# Qwiic_Joystick_v1_1_1.net
KiCad netlist of a schematic drawn in EAGLE
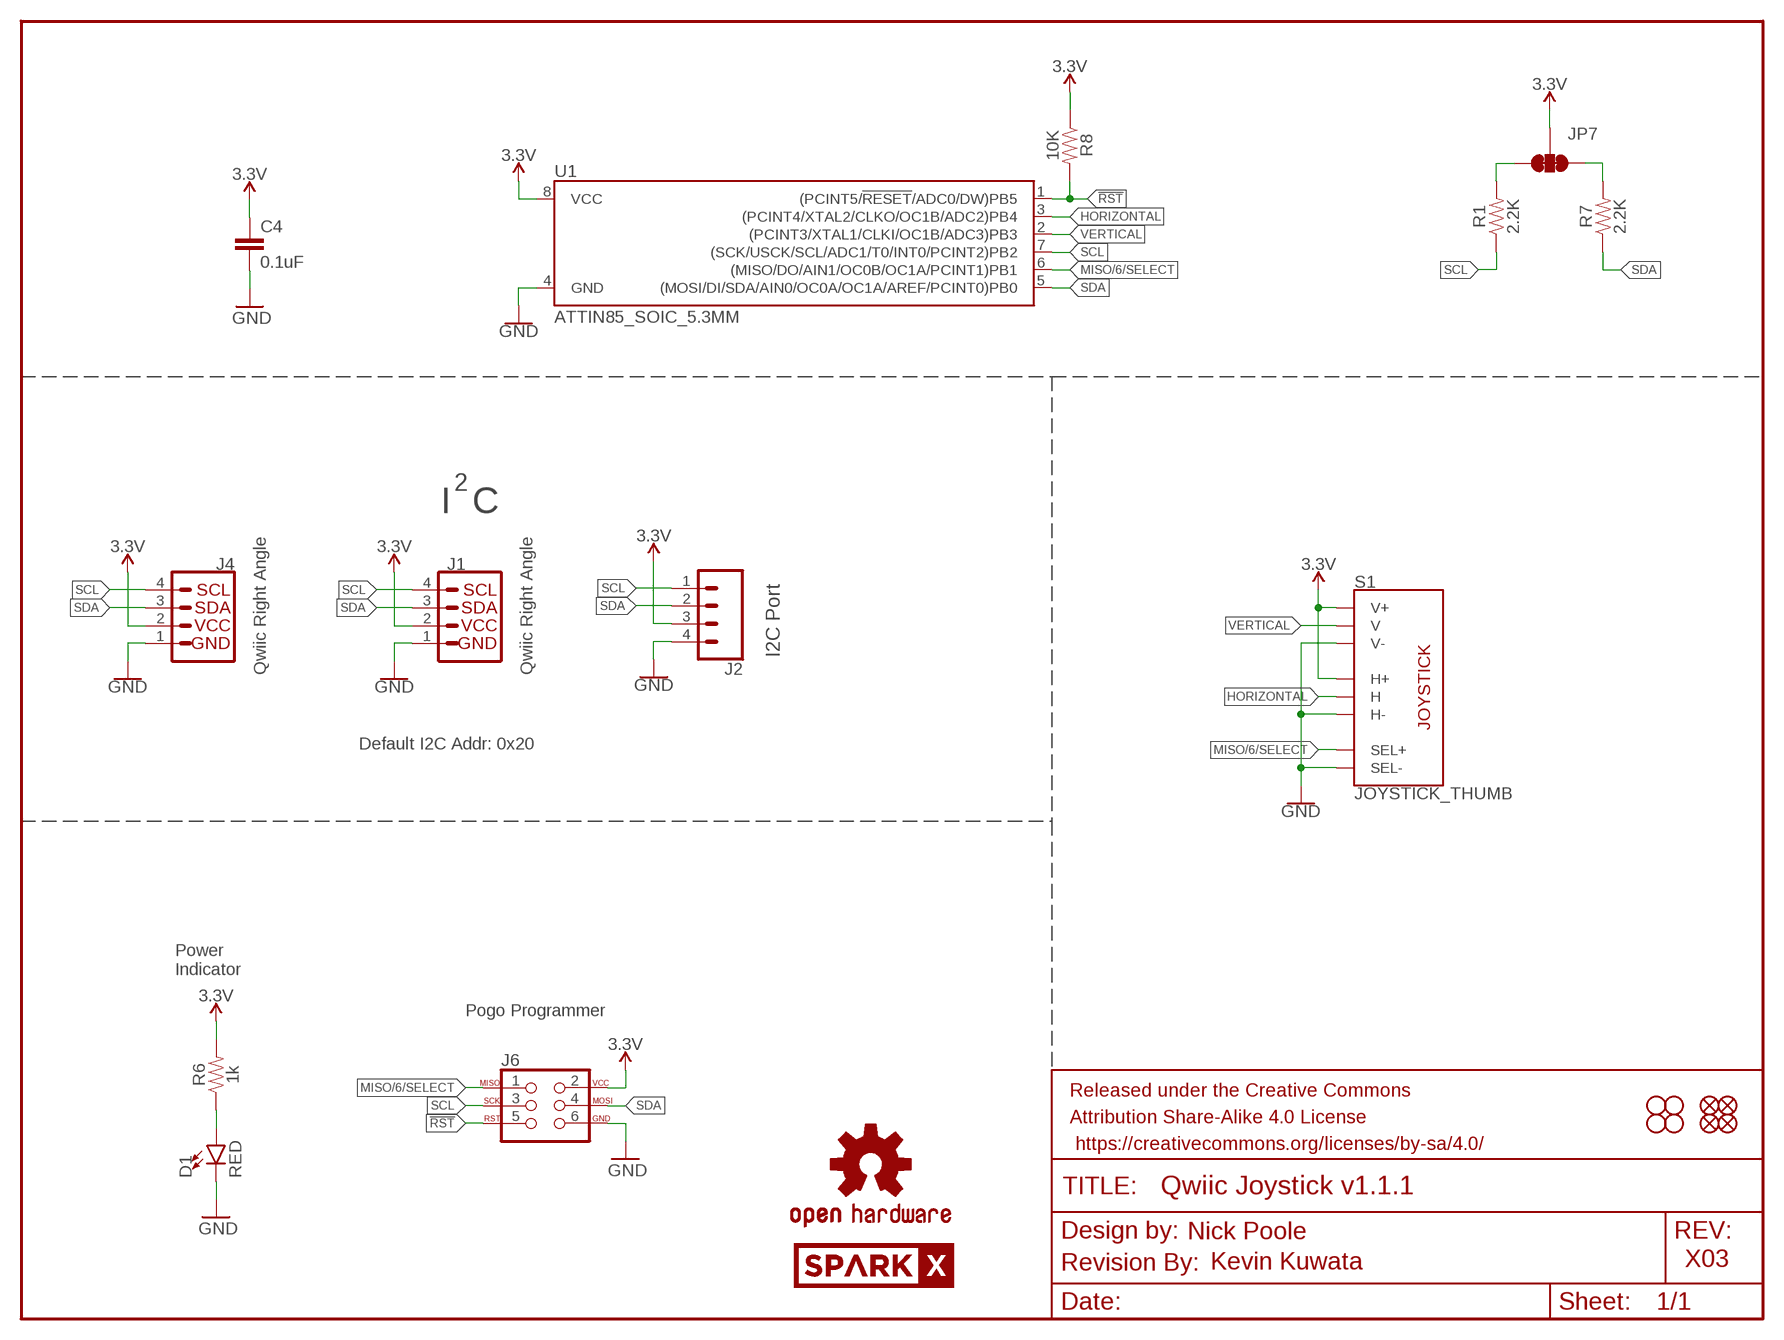
[diagram p0: schematic, sheet 1]

(export (version "E")
  (design (tool "Eeschema 10.0.6"))
  (components
    (comp (ref "C4")
      (value "0.1uF")
      (footprint "eagle-import:0603")
      (libsource (lib "eagle-import") (part "0.1UF-0603-25V-(+80/-20%)"))
    )
    (comp (ref "D1")
      (value "RED")
      (footprint "eagle-import:LED-0603")
      (libsource (lib "eagle-import") (part "LED-RED0603"))
    )
    (comp (ref "FRAME1")
      (value "FRAME-LETTER")
      (footprint "eagle-import:CREATIVE_COMMONS")
      (libsource (lib "eagle-import") (part "FRAME-LETTER"))
    )
    (comp (ref "H1")
      (value "STAND-OFF")
      (footprint "eagle-import:STAND-OFF")
      (libsource (lib "eagle-import") (part "STAND-OFF"))
    )
    (comp (ref "H2")
      (value "STAND-OFF")
      (footprint "eagle-import:STAND-OFF")
      (libsource (lib "eagle-import") (part "STAND-OFF"))
    )
    (comp (ref "H3")
      (value "STAND-OFF")
      (footprint "eagle-import:STAND-OFF")
      (libsource (lib "eagle-import") (part "STAND-OFF"))
    )
    (comp (ref "H4")
      (value "STAND-OFF")
      (footprint "eagle-import:STAND-OFF")
      (libsource (lib "eagle-import") (part "STAND-OFF"))
    )
    (comp (ref "J1")
      (value "Qwiic Right Angle")
      (footprint "eagle-import:1X04_1MM_RA")
      (libsource (lib "eagle-import") (part "I2C_STANDARDQWIIC"))
    )
    (comp (ref "J2")
      (value "CONN_041X04_NO_SILK")
      (footprint "eagle-import:1X04_NO_SILK")
      (libsource (lib "eagle-import") (part "CONN_041X04_NO_SILK"))
    )
    (comp (ref "J4")
      (value "Qwiic Right Angle")
      (footprint "eagle-import:1X04_1MM_RA")
      (libsource (lib "eagle-import") (part "I2C_STANDARDQWIIC"))
    )
    (comp (ref "J6")
      (value "AVR_SPI_PROG_3X2TESTPOINTS")
      (footprint "eagle-import:2X3_TEST_POINTS")
      (libsource (lib "eagle-import") (part "AVR_SPI_PROG_3X2TESTPOINTS"))
    )
    (comp (ref "JP1")
      (value "FIDUCIALUFIDUCIAL")
      (footprint "eagle-import:MICRO-FIDUCIAL")
      (libsource (lib "eagle-import") (part "FIDUCIALUFIDUCIAL"))
    )
    (comp (ref "JP2")
      (value "FIDUCIALUFIDUCIAL")
      (footprint "eagle-import:MICRO-FIDUCIAL")
      (libsource (lib "eagle-import") (part "FIDUCIALUFIDUCIAL"))
    )
    (comp (ref "JP3")
      (value "FIDUCIALUFIDUCIAL")
      (footprint "eagle-import:MICRO-FIDUCIAL")
      (libsource (lib "eagle-import") (part "FIDUCIALUFIDUCIAL"))
    )
    (comp (ref "JP6")
      (value "FIDUCIALUFIDUCIAL")
      (footprint "eagle-import:MICRO-FIDUCIAL")
      (libsource (lib "eagle-import") (part "FIDUCIALUFIDUCIAL"))
    )
    (comp (ref "JP7")
      (value "JUMPER-SMT_3_2-NC_TRACE_NO-SILK")
      (footprint "eagle-import:SMT-JUMPER_3_2-NC_TRACE_NO-SILK")
      (libsource (lib "eagle-import") (part "JUMPER-SMT_3_2-NC_TRACE_NO-SILK"))
    )
    (comp (ref "LOGO1")
      (value "OSHW-LOGOMINI")
      (footprint "eagle-import:OSHW-LOGO-MINI")
      (libsource (lib "eagle-import") (part "OSHW-LOGOMINI"))
    )
    (comp (ref "LOGO2")
      (value "REVISION")
      (footprint "eagle-import:REVISION")
      (libsource (lib "eagle-import") (part "REVISION"))
    )
    (comp (ref "R1")
      (value "2.2K")
      (footprint "eagle-import:0603")
      (libsource (lib "eagle-import") (part "4.7KOHM-0603-1/10W-1%"))
    )
    (comp (ref "R6")
      (value "1k")
      (footprint "eagle-import:0603")
      (libsource (lib "eagle-import") (part "1KOHM-0603-1/10W-1%"))
    )
    (comp (ref "R7")
      (value "2.2K")
      (footprint "eagle-import:0603")
      (libsource (lib "eagle-import") (part "4.7KOHM-0603-1/10W-1%"))
    )
    (comp (ref "R8")
      (value "10K")
      (footprint "eagle-import:0603")
      (libsource (lib "eagle-import") (part "330OHM-0603-1/10W-1%"))
    )
    (comp (ref "S1")
      (value "JOYSTICK_THUMB")
      (footprint "eagle-import:JOYSTICK")
      (libsource (lib "eagle-import") (part "JOYSTICK_THUMB"))
    )
    (comp (ref "U$1")
      (value "SPARKX-LOGO3")
      (footprint "eagle-import:SPARKX-SMALL")
      (libsource (lib "eagle-import") (part "SPARKX-LOGO3"))
    )
    (comp (ref "U$2")
      (value "SPARKX-LOGO3")
      (footprint "eagle-import:SPARKX-SMALL")
      (libsource (lib "eagle-import") (part "SPARKX-LOGO3"))
    )
    (comp (ref "U1")
      (value "ATTIN85_SOIC_5.3MM")
      (footprint "eagle-import:ATTINY85")
      (libsource (lib "eagle-import") (part "ATTIN85_SOIC_5.3MM"))
    )
  )
  (nets
    (net (code "1") (name "/~{RST}") (class "Default")
      (node (ref "J6") (pin "5") (pinfunction "5_5") (pintype "passive"))
      (node (ref "R8") (pin "2") (pinfunction "2_2") (pintype "passive"))
      (node (ref "U1") (pin "1") (pinfunction "(PCINT5/~{RESET}/ADC0/DW)PB5_1") (pintype "bidirectional"))
    )
    (net (code "2") (name "3.3V") (class "Default")
      (node (ref "C4") (pin "1") (pinfunction "1_1") (pintype "passive"))
      (node (ref "J1") (pin "2") (pinfunction "2_2") (pintype "power_in"))
      (node (ref "J2") (pin "3") (pinfunction "3_3") (pintype "passive"))
      (node (ref "J4") (pin "2") (pinfunction "2_2") (pintype "power_in"))
      (node (ref "J6") (pin "2") (pinfunction "2_2") (pintype "passive"))
      (node (ref "JP7") (pin "2") (pinfunction "2_2") (pintype "passive"))
      (node (ref "R6") (pin "2") (pinfunction "2_2") (pintype "passive"))
      (node (ref "R8") (pin "1") (pinfunction "1_1") (pintype "passive"))
      (node (ref "S1") (pin "H1") (pinfunction "H+_H1") (pintype "bidirectional"))
      (node (ref "S1") (pin "V1") (pinfunction "V+_V1") (pintype "bidirectional"))
      (node (ref "U1") (pin "8") (pinfunction "VCC_8") (pintype "bidirectional"))
    )
    (net (code "3") (name "GND") (class "Default")
      (node (ref "C4") (pin "2") (pinfunction "2_2") (pintype "passive"))
      (node (ref "D1") (pin "C") (pinfunction "C_C") (pintype "passive"))
      (node (ref "J1") (pin "1") (pinfunction "1_1") (pintype "power_in"))
      (node (ref "J2") (pin "4") (pinfunction "4_4") (pintype "passive"))
      (node (ref "J4") (pin "1") (pinfunction "1_1") (pintype "power_in"))
      (node (ref "J6") (pin "6") (pinfunction "6_6") (pintype "passive"))
      (node (ref "S1") (pin "B2A") (pinfunction "SEL-_B2A") (pintype "bidirectional"))
      (node (ref "S1") (pin "H3") (pinfunction "H-_H3") (pintype "bidirectional"))
      (node (ref "S1") (pin "V3") (pinfunction "V-_V3") (pintype "bidirectional"))
      (node (ref "U1") (pin "4") (pinfunction "GND_4") (pintype "bidirectional"))
    )
    (net (code "4") (name "HORIZONTAL") (class "Default")
      (node (ref "S1") (pin "H2") (pinfunction "H_H2") (pintype "bidirectional"))
      (node (ref "U1") (pin "3") (pinfunction "(PCINT4/XTAL2/CLKO/OC1B/ADC2)PB4_3") (pintype "bidirectional"))
    )
    (net (code "5") (name "MISO{slash}6{slash}SELECT") (class "Default")
      (node (ref "J6") (pin "1") (pinfunction "1_1") (pintype "passive"))
      (node (ref "S1") (pin "B1A") (pinfunction "SEL+_B1A") (pintype "bidirectional"))
      (node (ref "U1") (pin "6") (pinfunction "(MISO/DO/AIN1/OC0B/OC1A/PCINT1)PB1_6") (pintype "bidirectional"))
    )
    (net (code "6") (name "Net-(D1-PadA)") (class "Default")
      (node (ref "D1") (pin "A") (pinfunction "A_A") (pintype "passive"))
      (node (ref "R6") (pin "1") (pinfunction "1_1") (pintype "passive"))
    )
    (net (code "7") (name "Net-(JP7-Pad1)") (class "Default")
      (node (ref "JP7") (pin "1") (pinfunction "1_1") (pintype "passive"))
      (node (ref "R7") (pin "2") (pinfunction "2_2") (pintype "passive"))
    )
    (net (code "8") (name "Net-(JP7-Pad3)") (class "Default")
      (node (ref "JP7") (pin "3") (pinfunction "3_3") (pintype "passive"))
      (node (ref "R1") (pin "2") (pinfunction "2_2") (pintype "passive"))
    )
    (net (code "9") (name "SCL") (class "Default")
      (node (ref "J1") (pin "4") (pinfunction "4_4") (pintype "passive"))
      (node (ref "J2") (pin "1") (pinfunction "1_1") (pintype "passive"))
      (node (ref "J4") (pin "4") (pinfunction "4_4") (pintype "passive"))
      (node (ref "J6") (pin "3") (pinfunction "3_3") (pintype "passive"))
      (node (ref "R1") (pin "1") (pinfunction "1_1") (pintype "passive"))
      (node (ref "U1") (pin "7") (pinfunction "(SCK/USCK/SCL/ADC1/T0/INT0/PCINT2)PB2_7") (pintype "bidirectional"))
    )
    (net (code "10") (name "SDA") (class "Default")
      (node (ref "J1") (pin "3") (pinfunction "3_3") (pintype "passive"))
      (node (ref "J2") (pin "2") (pinfunction "2_2") (pintype "passive"))
      (node (ref "J4") (pin "3") (pinfunction "3_3") (pintype "passive"))
      (node (ref "J6") (pin "4") (pinfunction "4_4") (pintype "passive"))
      (node (ref "R7") (pin "1") (pinfunction "1_1") (pintype "passive"))
      (node (ref "U1") (pin "5") (pinfunction "(MOSI/DI/SDA/AIN0/OC0A/OC1A/AREF/PCINT0)PB0_5") (pintype "bidirectional"))
    )
    (net (code "11") (name "VERTICAL") (class "Default")
      (node (ref "S1") (pin "V2") (pinfunction "V_V2") (pintype "bidirectional"))
      (node (ref "U1") (pin "2") (pinfunction "(PCINT3/XTAL1/CLKI/OC1B/ADC3)PB3_2") (pintype "bidirectional"))
    )
  )
)
